# EasyEda_SCH_tally_light_-_led_matrix_202.net
KiCad netlist of a schematic drawn in EasyEDA
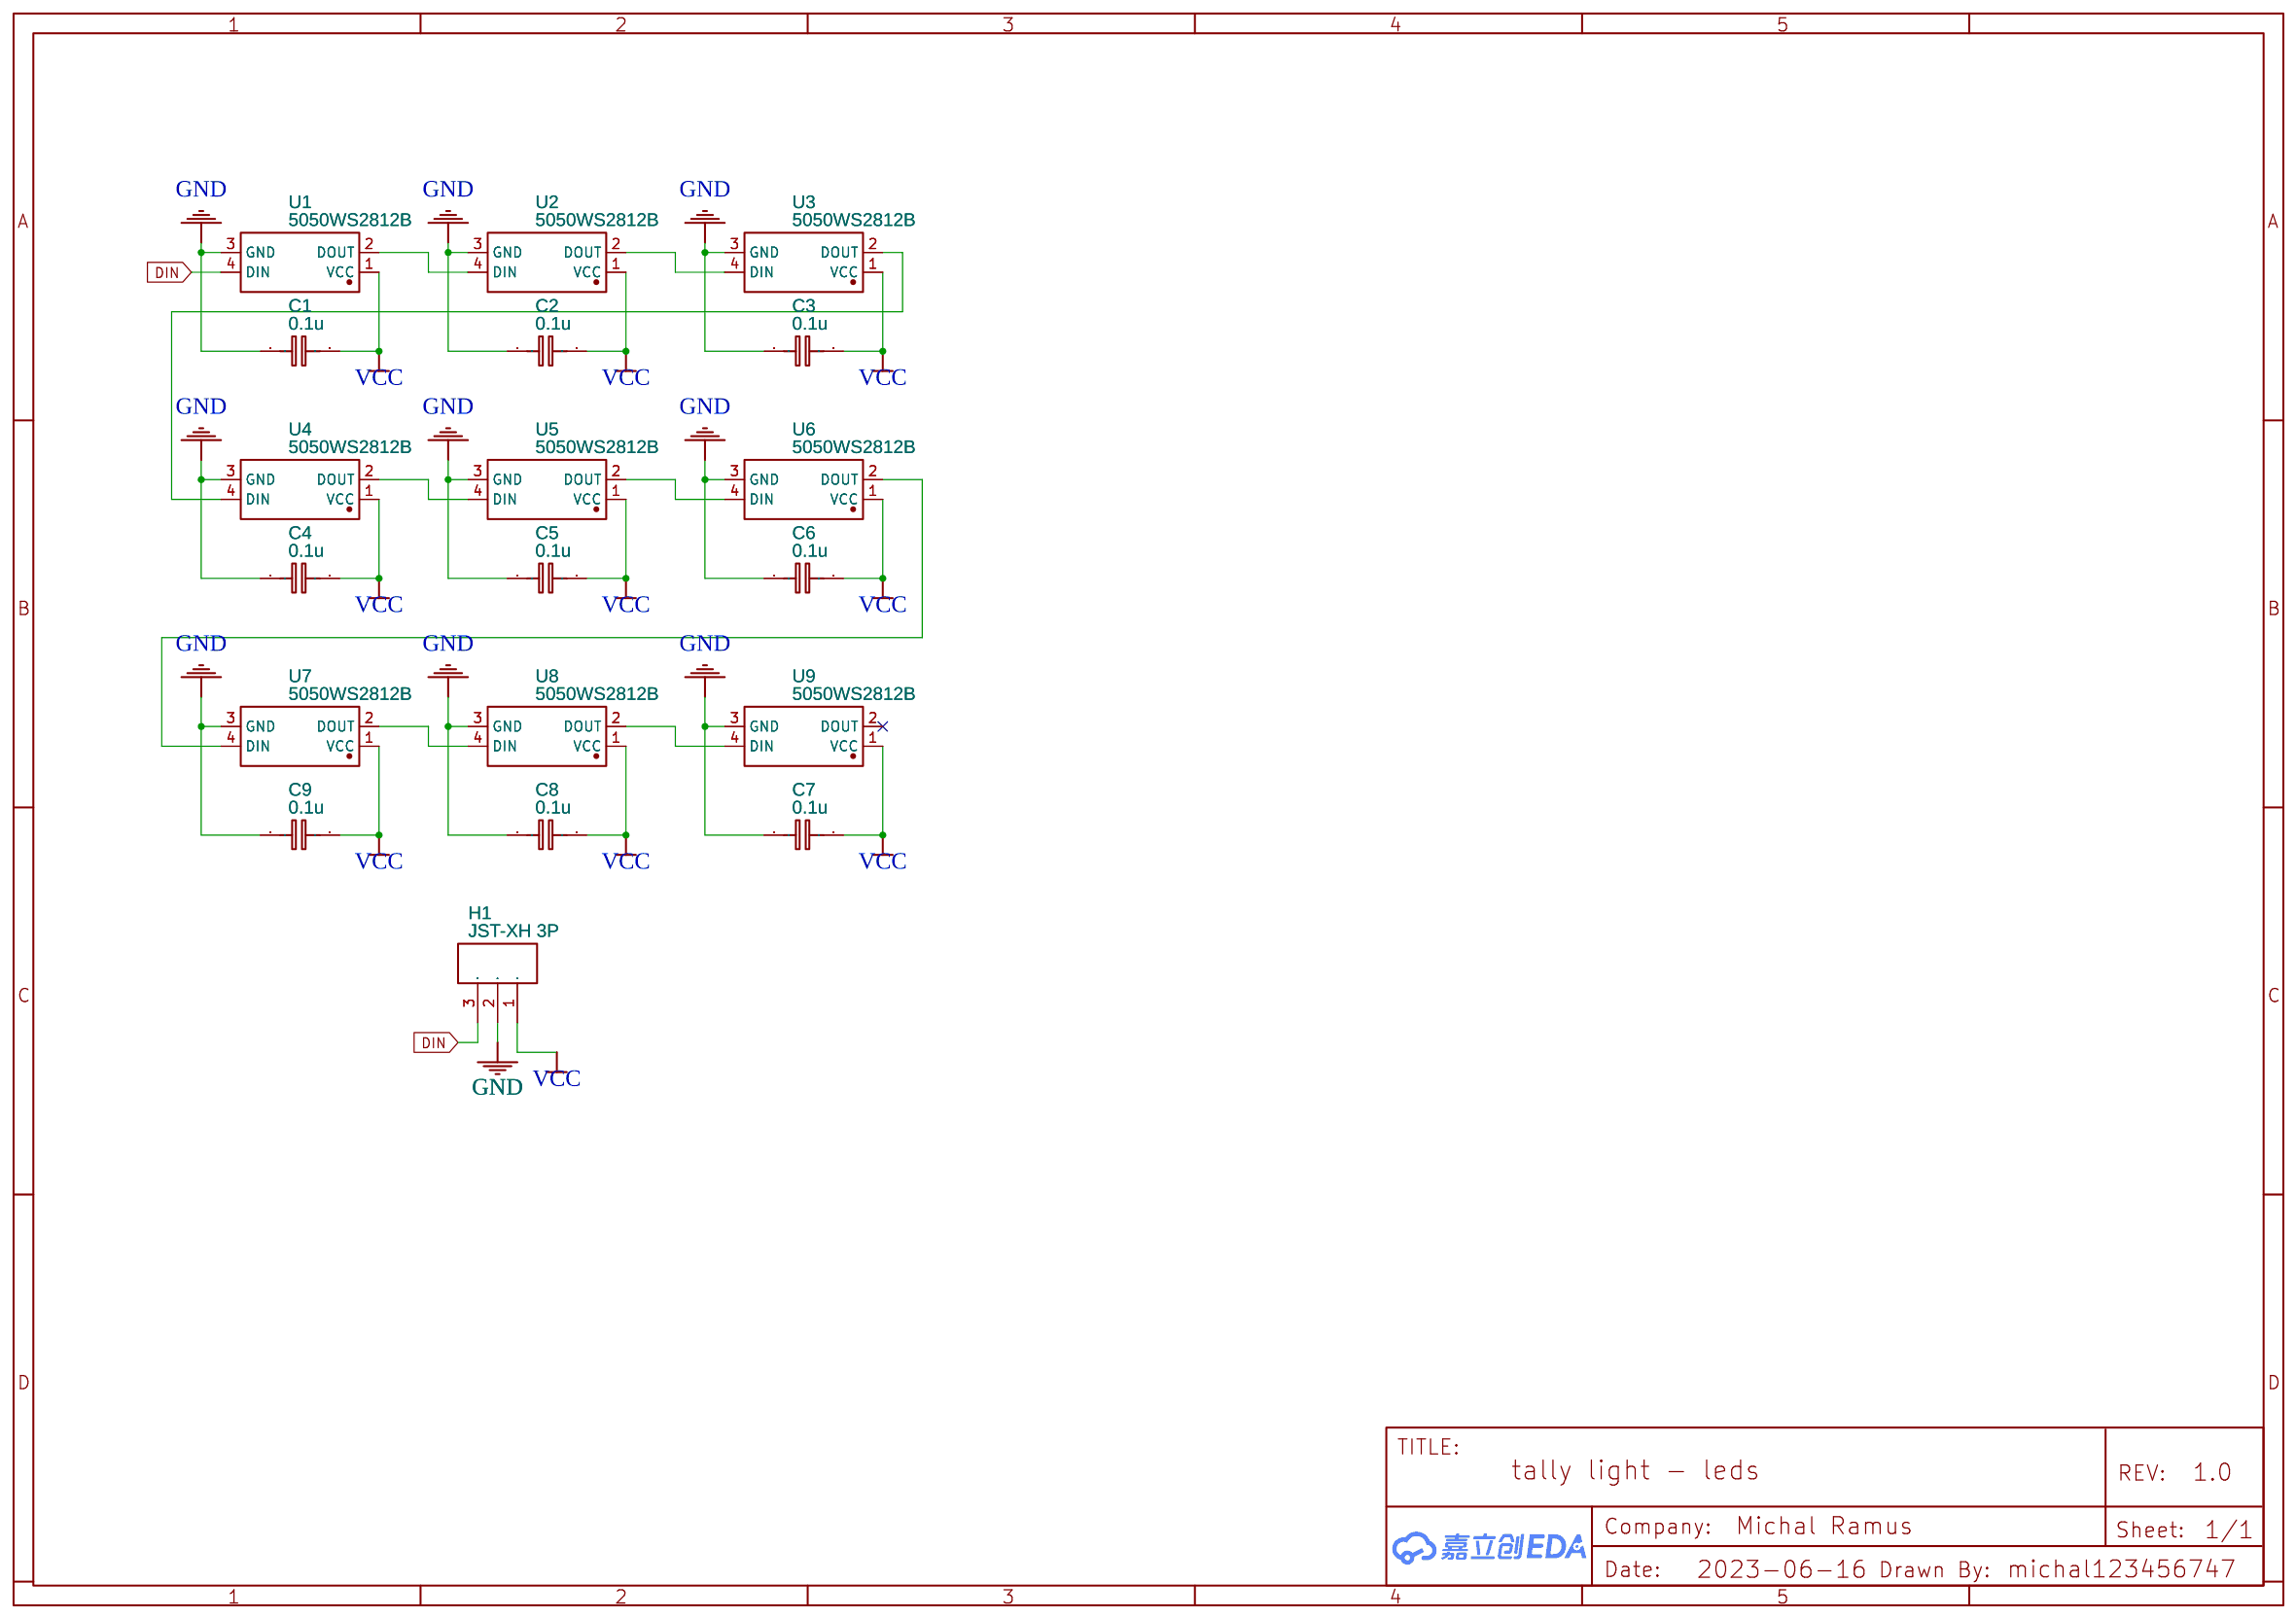
[diagram p0: schematic sheet]

(export (version "E")
  (design (tool "Eeschema 10.0.6"))
  (components
    (comp (ref "C1") (value "0.1u") (libsource (lib "") (part "C_0603_EU_1")))
    (comp (ref "C2") (value "0.1u") (libsource (lib "") (part "C_0603_EU_1")))
    (comp (ref "C3") (value "0.1u") (libsource (lib "") (part "C_0603_EU_1")))
    (comp (ref "C4") (value "0.1u") (libsource (lib "") (part "C_0603_EU_1")))
    (comp (ref "C5") (value "0.1u") (libsource (lib "") (part "C_0603_EU_1")))
    (comp (ref "C6") (value "0.1u") (libsource (lib "") (part "C_0603_EU_1")))
    (comp (ref "C7") (value "0.1u") (libsource (lib "") (part "C_0603_EU")))
    (comp (ref "C8") (value "0.1u") (libsource (lib "") (part "C_0603_EU")))
    (comp (ref "C9") (value "0.1u") (libsource (lib "") (part "C_0603_EU")))
    (comp (ref "H1") (value "JST-XH 3P") (libsource (lib "") (part "JST-XH 3P")))
    (comp (ref "U1") (value "5050WS2812B") (libsource (lib "") (part "5050WS2812B")))
    (comp (ref "U2") (value "5050WS2812B") (libsource (lib "") (part "5050WS2812B")))
    (comp (ref "U3") (value "5050WS2812B") (libsource (lib "") (part "5050WS2812B")))
    (comp (ref "U4") (value "5050WS2812B") (libsource (lib "") (part "5050WS2812B")))
    (comp (ref "U5") (value "5050WS2812B") (libsource (lib "") (part "5050WS2812B")))
    (comp (ref "U6") (value "5050WS2812B") (libsource (lib "") (part "5050WS2812B")))
    (comp (ref "U7") (value "5050WS2812B") (libsource (lib "") (part "5050WS2812B")))
    (comp (ref "U8") (value "5050WS2812B") (libsource (lib "") (part "5050WS2812B")))
    (comp (ref "U9") (value "5050WS2812B") (libsource (lib "") (part "5050WS2812B")))
  )
  (nets
    (net (code "1") (name "DIN") (class "Default")
      (node (ref "H1") (pin "3") (pinfunction "3_3") (pintype "unspecified"))
      (node (ref "U1") (pin "4") (pinfunction "DIN_4") (pintype "unspecified"))
    )
    (net (code "2") (name "GND") (class "Default")
      (node (ref "C1") (pin "1") (pinfunction "1_1") (pintype "unspecified"))
      (node (ref "C2") (pin "1") (pinfunction "1_1") (pintype "unspecified"))
      (node (ref "C3") (pin "1") (pinfunction "1_1") (pintype "unspecified"))
      (node (ref "C4") (pin "1") (pinfunction "1_1") (pintype "unspecified"))
      (node (ref "C5") (pin "1") (pinfunction "1_1") (pintype "unspecified"))
      (node (ref "C6") (pin "1") (pinfunction "1_1") (pintype "unspecified"))
      (node (ref "C7") (pin "1") (pinfunction "1_1") (pintype "unspecified"))
      (node (ref "C8") (pin "1") (pinfunction "1_1") (pintype "unspecified"))
      (node (ref "C9") (pin "1") (pinfunction "1_1") (pintype "unspecified"))
      (node (ref "H1") (pin "2") (pinfunction "2_2") (pintype "unspecified"))
      (node (ref "U1") (pin "3") (pinfunction "GND_3") (pintype "unspecified"))
      (node (ref "U2") (pin "3") (pinfunction "GND_3") (pintype "unspecified"))
      (node (ref "U3") (pin "3") (pinfunction "GND_3") (pintype "unspecified"))
      (node (ref "U4") (pin "3") (pinfunction "GND_3") (pintype "unspecified"))
      (node (ref "U5") (pin "3") (pinfunction "GND_3") (pintype "unspecified"))
      (node (ref "U6") (pin "3") (pinfunction "GND_3") (pintype "unspecified"))
      (node (ref "U7") (pin "3") (pinfunction "GND_3") (pintype "unspecified"))
      (node (ref "U8") (pin "3") (pinfunction "GND_3") (pintype "unspecified"))
      (node (ref "U9") (pin "3") (pinfunction "GND_3") (pintype "unspecified"))
    )
    (net (code "3") (name "Net-(U1-DOUT)") (class "Default")
      (node (ref "U1") (pin "2") (pinfunction "DOUT_2") (pintype "unspecified"))
      (node (ref "U2") (pin "4") (pinfunction "DIN_4") (pintype "unspecified"))
    )
    (net (code "4") (name "Net-(U2-DOUT)") (class "Default")
      (node (ref "U2") (pin "2") (pinfunction "DOUT_2") (pintype "unspecified"))
      (node (ref "U3") (pin "4") (pinfunction "DIN_4") (pintype "unspecified"))
    )
    (net (code "5") (name "Net-(U3-DOUT)") (class "Default")
      (node (ref "U3") (pin "2") (pinfunction "DOUT_2") (pintype "unspecified"))
      (node (ref "U4") (pin "4") (pinfunction "DIN_4") (pintype "unspecified"))
    )
    (net (code "6") (name "Net-(U4-DOUT)") (class "Default")
      (node (ref "U4") (pin "2") (pinfunction "DOUT_2") (pintype "unspecified"))
      (node (ref "U5") (pin "4") (pinfunction "DIN_4") (pintype "unspecified"))
    )
    (net (code "7") (name "Net-(U5-DOUT)") (class "Default")
      (node (ref "U5") (pin "2") (pinfunction "DOUT_2") (pintype "unspecified"))
      (node (ref "U6") (pin "4") (pinfunction "DIN_4") (pintype "unspecified"))
    )
    (net (code "8") (name "Net-(U6-DOUT)") (class "Default")
      (node (ref "U6") (pin "2") (pinfunction "DOUT_2") (pintype "unspecified"))
      (node (ref "U7") (pin "4") (pinfunction "DIN_4") (pintype "unspecified"))
    )
    (net (code "9") (name "Net-(U7-DOUT)") (class "Default")
      (node (ref "U7") (pin "2") (pinfunction "DOUT_2") (pintype "unspecified"))
      (node (ref "U8") (pin "4") (pinfunction "DIN_4") (pintype "unspecified"))
    )
    (net (code "10") (name "Net-(U8-DOUT)") (class "Default")
      (node (ref "U8") (pin "2") (pinfunction "DOUT_2") (pintype "unspecified"))
      (node (ref "U9") (pin "4") (pinfunction "DIN_4") (pintype "unspecified"))
    )
    (net (code "11") (name "VCC") (class "Default")
      (node (ref "C1") (pin "2") (pinfunction "2_2") (pintype "unspecified"))
      (node (ref "C2") (pin "2") (pinfunction "2_2") (pintype "unspecified"))
      (node (ref "C3") (pin "2") (pinfunction "2_2") (pintype "unspecified"))
      (node (ref "C4") (pin "2") (pinfunction "2_2") (pintype "unspecified"))
      (node (ref "C5") (pin "2") (pinfunction "2_2") (pintype "unspecified"))
      (node (ref "C6") (pin "2") (pinfunction "2_2") (pintype "unspecified"))
      (node (ref "C7") (pin "2") (pinfunction "2_2") (pintype "unspecified"))
      (node (ref "C8") (pin "2") (pinfunction "2_2") (pintype "unspecified"))
      (node (ref "C9") (pin "2") (pinfunction "2_2") (pintype "unspecified"))
      (node (ref "H1") (pin "1") (pinfunction "1_1") (pintype "unspecified"))
      (node (ref "U1") (pin "1") (pinfunction "VCC_1") (pintype "unspecified"))
      (node (ref "U2") (pin "1") (pinfunction "VCC_1") (pintype "unspecified"))
      (node (ref "U3") (pin "1") (pinfunction "VCC_1") (pintype "unspecified"))
      (node (ref "U4") (pin "1") (pinfunction "VCC_1") (pintype "unspecified"))
      (node (ref "U5") (pin "1") (pinfunction "VCC_1") (pintype "unspecified"))
      (node (ref "U6") (pin "1") (pinfunction "VCC_1") (pintype "unspecified"))
      (node (ref "U7") (pin "1") (pinfunction "VCC_1") (pintype "unspecified"))
      (node (ref "U8") (pin "1") (pinfunction "VCC_1") (pintype "unspecified"))
      (node (ref "U9") (pin "1") (pinfunction "VCC_1") (pintype "unspecified"))
    )
    (net (code "12") (name "unconnected-(U9-DOUT-Pad2)") (class "Default")
      (node (ref "U9") (pin "2") (pinfunction "DOUT_2") (pintype "unspecified+no_connect"))
    )
  )
)
